# 4_AT_START_F403A_V1_2_Connectors.net
KiCad netlist of a schematic drawn in Altium Designer
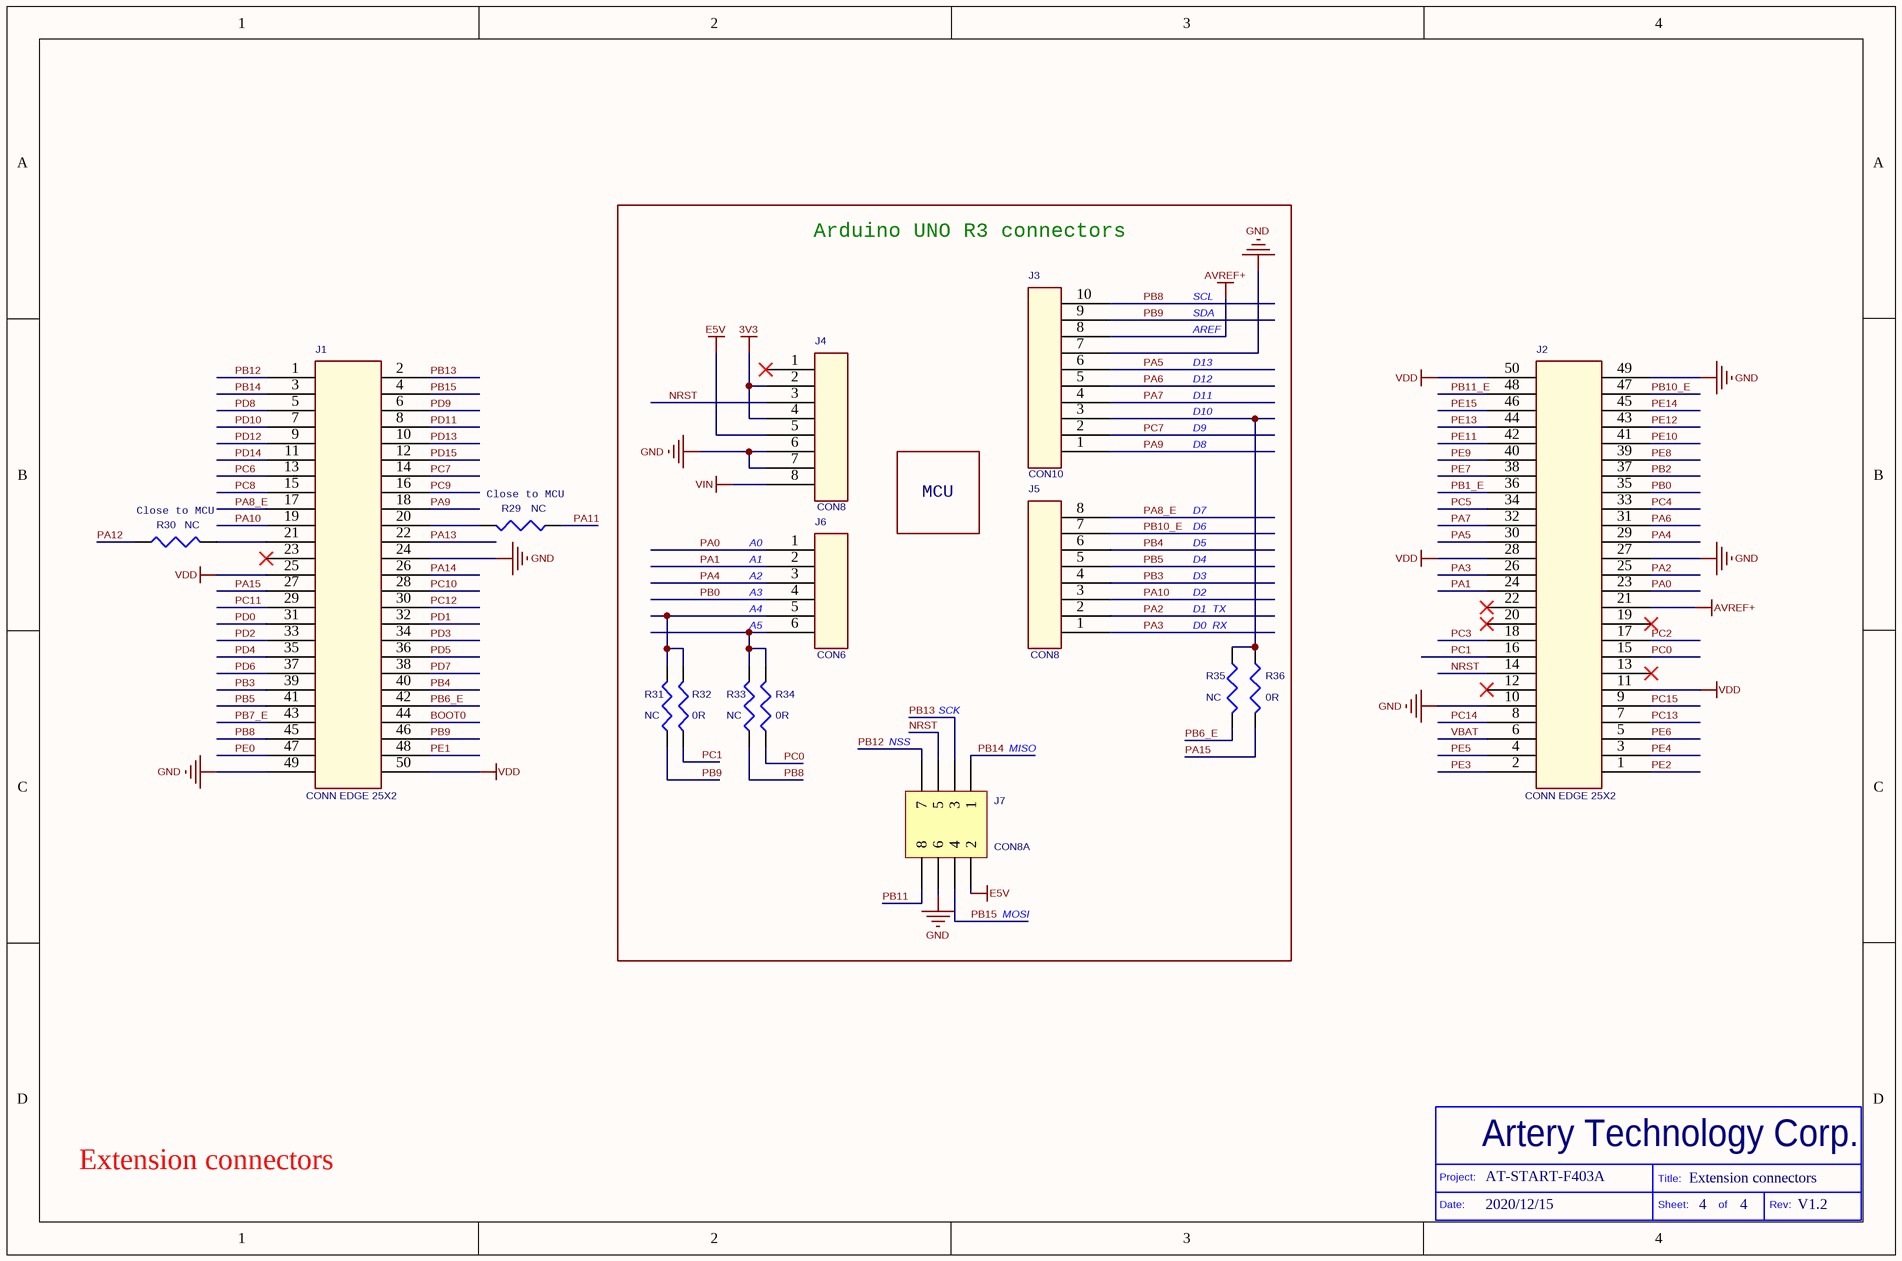
[diagram p0: 4_AT_START_F403A_V1.2_Connectors.SchDoc]

(export (version "E")
  (design (tool "Eeschema 10.0.6"))
  (components
    (comp (ref "J1")
      (value "CONN EDGE 25X2")
      (footprint "HEAD2*25")
      (libsource (lib "SCM_START_402F") (part "CONN EDGE 25X2"))
    )
    (comp (ref "J2")
      (value "CONN EDGE 25X2")
      (footprint "HEAD2*25")
      (libsource (lib "") (part "CONN EDGE 25X2_1"))
    )
    (comp (ref "J3") (value "CON10") (footprint "HDR1X10 - 2#") (libsource (lib "*") (part "CON10_0")))
    (comp (ref "J4") (value "CON8") (footprint "HDR1X8 - 2#") (libsource (lib "") (part "CON8_1")))
    (comp (ref "J5") (value "CON8") (footprint "HDR1X8 - 2#") (libsource (lib "*") (part "CON8")))
    (comp (ref "J6") (value "CON6") (footprint "HDR1X6 -2#") (libsource (lib "*") (part "CON6")))
    (comp (ref "J7")
      (value "CON8A")
      (footprint "HDR2X4")
      (description "Header, 4-Pin, Dual row")
      (fields (field (name "PUBLISHER") "Altium Limited"))
      (libsource (lib "Miscellaneous Connectors") (part "Header 4X2"))
    )
    (comp (ref "R29") (value "NC") (libsource (lib "*") (part "470,1/10W,1%,SMD0603")))
    (comp (ref "R30") (value "NC") (libsource (lib "*") (part "470,1/10W,1%,SMD0603")))
    (comp (ref "R31") (value "NC") (libsource (lib "*") (part "10K,1/10W,1%,SMD0603_Dup1")))
    (comp (ref "R32") (value "0R") (libsource (lib "*") (part "10K,1/10W,1%,SMD0603_Dup1")))
    (comp (ref "R33") (value "NC") (libsource (lib "*") (part "10K,1/10W,1%,SMD0603_Dup1")))
    (comp (ref "R34") (value "0R") (libsource (lib "*") (part "10K,1/10W,1%,SMD0603_Dup1")))
    (comp (ref "R35") (value "NC") (libsource (lib "*") (part "10K,1/10W,1%,SMD0603_Dup1")))
    (comp (ref "R36") (value "0R") (libsource (lib "*") (part "10K,1/10W,1%,SMD0603_Dup1")))
  )
  (nets
    (net (code "1") (name "/A0") (class "Default")
      (node (ref "J2") (pin "23") (pinfunction "23_23") (pintype "passive"))
      (node (ref "J6") (pin "1") (pinfunction "1_1") (pintype "passive"))
    )
    (net (code "2") (name "/A1") (class "Default")
      (node (ref "J2") (pin "24") (pinfunction "24_24") (pintype "passive"))
      (node (ref "J6") (pin "2") (pinfunction "2_2") (pintype "passive"))
    )
    (net (code "3") (name "/A2") (class "Default")
      (node (ref "J2") (pin "29") (pinfunction "29_29") (pintype "passive"))
      (node (ref "J6") (pin "3") (pinfunction "3_3") (pintype "passive"))
    )
    (net (code "4") (name "/A3") (class "Default")
      (node (ref "J2") (pin "35") (pinfunction "35_35") (pintype "passive"))
      (node (ref "J6") (pin "4") (pinfunction "4_4") (pintype "passive"))
    )
    (net (code "5") (name "/A4") (class "Default")
      (node (ref "J6") (pin "5") (pinfunction "5_5") (pintype "passive"))
      (node (ref "R31") (pin "2") (pinfunction "2_2") (pintype "passive"))
      (node (ref "R32") (pin "2") (pinfunction "2_2") (pintype "passive"))
    )
    (net (code "6") (name "/A5") (class "Default")
      (node (ref "J6") (pin "6") (pinfunction "6_6") (pintype "passive"))
      (node (ref "R33") (pin "2") (pinfunction "2_2") (pintype "passive"))
      (node (ref "R34") (pin "2") (pinfunction "2_2") (pintype "passive"))
    )
    (net (code "7") (name "/BOOT0") (class "Default")
      (node (ref "J1") (pin "44") (pinfunction "44_44") (pintype "passive"))
    )
    (net (code "8") (name "/D0") (class "Default")
      (node (ref "J2") (pin "26") (pinfunction "26_26") (pintype "passive"))
      (node (ref "J5") (pin "1") (pinfunction "1_1") (pintype "passive"))
    )
    (net (code "9") (name "/D1") (class "Default")
      (node (ref "J2") (pin "25") (pinfunction "25_25") (pintype "passive"))
      (node (ref "J5") (pin "2") (pinfunction "2_2") (pintype "passive"))
    )
    (net (code "10") (name "/D2") (class "Default")
      (node (ref "J1") (pin "19") (pinfunction "19_19") (pintype "passive"))
      (node (ref "J5") (pin "3") (pinfunction "3_3") (pintype "passive"))
    )
    (net (code "11") (name "/D3") (class "Default")
      (node (ref "J1") (pin "39") (pinfunction "39_39") (pintype "passive"))
      (node (ref "J5") (pin "4") (pinfunction "4_4") (pintype "passive"))
    )
    (net (code "12") (name "/D4") (class "Default")
      (node (ref "J1") (pin "41") (pinfunction "41_41") (pintype "passive"))
      (node (ref "J5") (pin "5") (pinfunction "5_5") (pintype "passive"))
    )
    (net (code "13") (name "/D5") (class "Default")
      (node (ref "J1") (pin "40") (pinfunction "40_40") (pintype "passive"))
      (node (ref "J5") (pin "6") (pinfunction "6_6") (pintype "passive"))
    )
    (net (code "14") (name "/D6") (class "Default")
      (node (ref "J2") (pin "47") (pinfunction "47_47") (pintype "passive"))
      (node (ref "J5") (pin "7") (pinfunction "7_7") (pintype "passive"))
    )
    (net (code "15") (name "/D7") (class "Default")
      (node (ref "J1") (pin "17") (pinfunction "17_17") (pintype "passive"))
      (node (ref "J5") (pin "8") (pinfunction "8_8") (pintype "passive"))
    )
    (net (code "16") (name "/D8") (class "Default")
      (node (ref "J1") (pin "18") (pinfunction "18_18") (pintype "passive"))
      (node (ref "J3") (pin "1") (pinfunction "1_1") (pintype "passive"))
    )
    (net (code "17") (name "/D9") (class "Default")
      (node (ref "J1") (pin "14") (pinfunction "14_14") (pintype "passive"))
      (node (ref "J3") (pin "2") (pinfunction "2_2") (pintype "passive"))
    )
    (net (code "18") (name "/D10") (class "Default")
      (node (ref "J3") (pin "3") (pinfunction "3_3") (pintype "passive"))
      (node (ref "R35") (pin "1") (pinfunction "1_1") (pintype "passive"))
      (node (ref "R36") (pin "1") (pinfunction "1_1") (pintype "passive"))
    )
    (net (code "19") (name "/D11") (class "Default")
      (node (ref "J2") (pin "32") (pinfunction "32_32") (pintype "passive"))
      (node (ref "J3") (pin "4") (pinfunction "4_4") (pintype "passive"))
    )
    (net (code "20") (name "/D12") (class "Default")
      (node (ref "J2") (pin "31") (pinfunction "31_31") (pintype "passive"))
      (node (ref "J3") (pin "5") (pinfunction "5_5") (pintype "passive"))
    )
    (net (code "21") (name "/D13") (class "Default")
      (node (ref "J2") (pin "30") (pinfunction "30_30") (pintype "passive"))
      (node (ref "J3") (pin "6") (pinfunction "6_6") (pintype "passive"))
    )
    (net (code "22") (name "/NRST") (class "Default")
      (node (ref "J2") (pin "14") (pinfunction "14_14") (pintype "passive"))
      (node (ref "J4") (pin "3") (pinfunction "3_3") (pintype "passive"))
      (node (ref "J7") (pin "5") (pinfunction "5_5") (pintype "passive"))
    )
    (net (code "23") (name "/PA11") (class "Default")
      (node (ref "R29") (pin "1") (pinfunction "1_1") (pintype "passive"))
    )
    (net (code "24") (name "/PA12") (class "Default")
      (node (ref "R30") (pin "1") (pinfunction "1_1") (pintype "passive"))
    )
    (net (code "25") (name "/PA13") (class "Default")
      (node (ref "J1") (pin "22") (pinfunction "22_22") (pintype "passive"))
    )
    (net (code "26") (name "/PA14") (class "Default")
      (node (ref "J1") (pin "26") (pinfunction "26_26") (pintype "passive"))
    )
    (net (code "27") (name "/PA15") (class "Default")
      (node (ref "J1") (pin "27") (pinfunction "27_27") (pintype "passive"))
      (node (ref "R36") (pin "2") (pinfunction "2_2") (pintype "passive"))
    )
    (net (code "28") (name "/PB1_E") (class "Default")
      (node (ref "J2") (pin "36") (pinfunction "36_36") (pintype "passive"))
    )
    (net (code "29") (name "/PB2") (class "Default")
      (node (ref "J2") (pin "37") (pinfunction "37_37") (pintype "passive"))
    )
    (net (code "30") (name "/PB6_E") (class "Default")
      (node (ref "J1") (pin "42") (pinfunction "42_42") (pintype "passive"))
      (node (ref "R35") (pin "2") (pinfunction "2_2") (pintype "passive"))
    )
    (net (code "31") (name "/PB7_E") (class "Default")
      (node (ref "J1") (pin "43") (pinfunction "43_43") (pintype "passive"))
    )
    (net (code "32") (name "/PB8") (class "Default")
      (node (ref "J1") (pin "45") (pinfunction "45_45") (pintype "passive"))
      (node (ref "J3") (pin "10") (pinfunction "10_10") (pintype "passive"))
      (node (ref "R33") (pin "1") (pinfunction "1_1") (pintype "passive"))
    )
    (net (code "33") (name "/PB9") (class "Default")
      (node (ref "J1") (pin "46") (pinfunction "46_46") (pintype "passive"))
      (node (ref "J3") (pin "9") (pinfunction "9_9") (pintype "passive"))
      (node (ref "R31") (pin "1") (pinfunction "1_1") (pintype "passive"))
    )
    (net (code "34") (name "/PB11") (class "Default")
      (node (ref "J7") (pin "8") (pinfunction "8_8") (pintype "passive"))
    )
    (net (code "35") (name "/PB11_E") (class "Default")
      (node (ref "J2") (pin "48") (pinfunction "48_48") (pintype "passive"))
    )
    (net (code "36") (name "/PB12") (class "Default")
      (node (ref "J1") (pin "1") (pinfunction "1_1") (pintype "passive"))
      (node (ref "J7") (pin "7") (pinfunction "7_7") (pintype "passive"))
    )
    (net (code "37") (name "/PB13") (class "Default")
      (node (ref "J1") (pin "2") (pinfunction "2_2") (pintype "passive"))
      (node (ref "J7") (pin "3") (pinfunction "3_3") (pintype "passive"))
    )
    (net (code "38") (name "/PB14") (class "Default")
      (node (ref "J1") (pin "3") (pinfunction "3_3") (pintype "passive"))
      (node (ref "J7") (pin "1") (pinfunction "1_1") (pintype "passive"))
    )
    (net (code "39") (name "/PB15") (class "Default")
      (node (ref "J1") (pin "4") (pinfunction "4_4") (pintype "passive"))
      (node (ref "J7") (pin "4") (pinfunction "4_4") (pintype "passive"))
    )
    (net (code "40") (name "/PC0") (class "Default")
      (node (ref "J2") (pin "15") (pinfunction "15_15") (pintype "passive"))
      (node (ref "R34") (pin "1") (pinfunction "1_1") (pintype "passive"))
    )
    (net (code "41") (name "/PC1") (class "Default")
      (node (ref "J2") (pin "16") (pinfunction "16_16") (pintype "passive"))
      (node (ref "R32") (pin "1") (pinfunction "1_1") (pintype "passive"))
    )
    (net (code "42") (name "/PC2") (class "Default")
      (node (ref "J2") (pin "17") (pinfunction "17_17") (pintype "passive"))
    )
    (net (code "43") (name "/PC3") (class "Default")
      (node (ref "J2") (pin "18") (pinfunction "18_18") (pintype "passive"))
    )
    (net (code "44") (name "/PC4") (class "Default")
      (node (ref "J2") (pin "33") (pinfunction "33_33") (pintype "passive"))
    )
    (net (code "45") (name "/PC5") (class "Default")
      (node (ref "J2") (pin "34") (pinfunction "34_34") (pintype "passive"))
    )
    (net (code "46") (name "/PC6") (class "Default")
      (node (ref "J1") (pin "13") (pinfunction "13_13") (pintype "passive"))
    )
    (net (code "47") (name "/PC8") (class "Default")
      (node (ref "J1") (pin "15") (pinfunction "15_15") (pintype "passive"))
    )
    (net (code "48") (name "/PC9") (class "Default")
      (node (ref "J1") (pin "16") (pinfunction "16_16") (pintype "passive"))
    )
    (net (code "49") (name "/PC10") (class "Default")
      (node (ref "J1") (pin "28") (pinfunction "28_28") (pintype "passive"))
    )
    (net (code "50") (name "/PC11") (class "Default")
      (node (ref "J1") (pin "29") (pinfunction "29_29") (pintype "passive"))
    )
    (net (code "51") (name "/PC12") (class "Default")
      (node (ref "J1") (pin "30") (pinfunction "30_30") (pintype "passive"))
    )
    (net (code "52") (name "/PC13") (class "Default")
      (node (ref "J2") (pin "7") (pinfunction "7_7") (pintype "passive"))
    )
    (net (code "53") (name "/PC14") (class "Default")
      (node (ref "J2") (pin "8") (pinfunction "8_8") (pintype "passive"))
    )
    (net (code "54") (name "/PC15") (class "Default")
      (node (ref "J2") (pin "9") (pinfunction "9_9") (pintype "passive"))
    )
    (net (code "55") (name "/PD0") (class "Default")
      (node (ref "J1") (pin "31") (pinfunction "31_31") (pintype "passive"))
    )
    (net (code "56") (name "/PD1") (class "Default")
      (node (ref "J1") (pin "32") (pinfunction "32_32") (pintype "passive"))
    )
    (net (code "57") (name "/PD2") (class "Default")
      (node (ref "J1") (pin "33") (pinfunction "33_33") (pintype "passive"))
    )
    (net (code "58") (name "/PD3") (class "Default")
      (node (ref "J1") (pin "34") (pinfunction "34_34") (pintype "passive"))
    )
    (net (code "59") (name "/PD4") (class "Default")
      (node (ref "J1") (pin "35") (pinfunction "35_35") (pintype "passive"))
    )
    (net (code "60") (name "/PD5") (class "Default")
      (node (ref "J1") (pin "36") (pinfunction "36_36") (pintype "passive"))
    )
    (net (code "61") (name "/PD6") (class "Default")
      (node (ref "J1") (pin "37") (pinfunction "37_37") (pintype "passive"))
    )
    (net (code "62") (name "/PD7") (class "Default")
      (node (ref "J1") (pin "38") (pinfunction "38_38") (pintype "passive"))
    )
    (net (code "63") (name "/PD8") (class "Default")
      (node (ref "J1") (pin "5") (pinfunction "5_5") (pintype "passive"))
    )
    (net (code "64") (name "/PD9") (class "Default")
      (node (ref "J1") (pin "6") (pinfunction "6_6") (pintype "passive"))
    )
    (net (code "65") (name "/PD10") (class "Default")
      (node (ref "J1") (pin "7") (pinfunction "7_7") (pintype "passive"))
    )
    (net (code "66") (name "/PD11") (class "Default")
      (node (ref "J1") (pin "8") (pinfunction "8_8") (pintype "passive"))
    )
    (net (code "67") (name "/PD12") (class "Default")
      (node (ref "J1") (pin "9") (pinfunction "9_9") (pintype "passive"))
    )
    (net (code "68") (name "/PD13") (class "Default")
      (node (ref "J1") (pin "10") (pinfunction "10_10") (pintype "passive"))
    )
    (net (code "69") (name "/PD14") (class "Default")
      (node (ref "J1") (pin "11") (pinfunction "11_11") (pintype "passive"))
    )
    (net (code "70") (name "/PD15") (class "Default")
      (node (ref "J1") (pin "12") (pinfunction "12_12") (pintype "passive"))
    )
    (net (code "71") (name "/PE0") (class "Default")
      (node (ref "J1") (pin "47") (pinfunction "47_47") (pintype "passive"))
    )
    (net (code "72") (name "/PE1") (class "Default")
      (node (ref "J1") (pin "48") (pinfunction "48_48") (pintype "passive"))
    )
    (net (code "73") (name "/PE2") (class "Default")
      (node (ref "J2") (pin "1") (pinfunction "1_1") (pintype "passive"))
    )
    (net (code "74") (name "/PE3") (class "Default")
      (node (ref "J2") (pin "2") (pinfunction "2_2") (pintype "passive"))
    )
    (net (code "75") (name "/PE4") (class "Default")
      (node (ref "J2") (pin "3") (pinfunction "3_3") (pintype "passive"))
    )
    (net (code "76") (name "/PE5") (class "Default")
      (node (ref "J2") (pin "4") (pinfunction "4_4") (pintype "passive"))
    )
    (net (code "77") (name "/PE6") (class "Default")
      (node (ref "J2") (pin "5") (pinfunction "5_5") (pintype "passive"))
    )
    (net (code "78") (name "/PE7") (class "Default")
      (node (ref "J2") (pin "38") (pinfunction "38_38") (pintype "passive"))
    )
    (net (code "79") (name "/PE8") (class "Default")
      (node (ref "J2") (pin "39") (pinfunction "39_39") (pintype "passive"))
    )
    (net (code "80") (name "/PE9") (class "Default")
      (node (ref "J2") (pin "40") (pinfunction "40_40") (pintype "passive"))
    )
    (net (code "81") (name "/PE10") (class "Default")
      (node (ref "J2") (pin "41") (pinfunction "41_41") (pintype "passive"))
    )
    (net (code "82") (name "/PE11") (class "Default")
      (node (ref "J2") (pin "42") (pinfunction "42_42") (pintype "passive"))
    )
    (net (code "83") (name "/PE12") (class "Default")
      (node (ref "J2") (pin "43") (pinfunction "43_43") (pintype "passive"))
    )
    (net (code "84") (name "/PE13") (class "Default")
      (node (ref "J2") (pin "44") (pinfunction "44_44") (pintype "passive"))
    )
    (net (code "85") (name "/PE14") (class "Default")
      (node (ref "J2") (pin "45") (pinfunction "45_45") (pintype "passive"))
    )
    (net (code "86") (name "/PE15") (class "Default")
      (node (ref "J2") (pin "46") (pinfunction "46_46") (pintype "passive"))
    )
    (net (code "87") (name "/VBAT") (class "Default")
      (node (ref "J2") (pin "6") (pinfunction "6_6") (pintype "passive"))
    )
    (net (code "88") (name "3V3") (class "Default")
      (node (ref "J4") (pin "2") (pinfunction "2_2") (pintype "passive"))
      (node (ref "J4") (pin "4") (pinfunction "4_4") (pintype "passive"))
    )
    (net (code "89") (name "AVREF+") (class "Default")
      (node (ref "J2") (pin "21") (pinfunction "21_21") (pintype "passive"))
      (node (ref "J3") (pin "8") (pinfunction "8_8") (pintype "passive"))
    )
    (net (code "90") (name "E5V") (class "Default")
      (node (ref "J4") (pin "5") (pinfunction "5_5") (pintype "passive"))
      (node (ref "J7") (pin "2") (pinfunction "2_2") (pintype "passive"))
    )
    (net (code "91") (name "GND") (class "Default")
      (node (ref "J1") (pin "24") (pinfunction "24_24") (pintype "passive"))
      (node (ref "J1") (pin "49") (pinfunction "49_49") (pintype "passive"))
      (node (ref "J2") (pin "10") (pinfunction "10_10") (pintype "passive"))
      (node (ref "J2") (pin "27") (pinfunction "27_27") (pintype "passive"))
      (node (ref "J2") (pin "49") (pinfunction "49_49") (pintype "passive"))
      (node (ref "J3") (pin "7") (pinfunction "7_7") (pintype "passive"))
      (node (ref "J4") (pin "6") (pinfunction "6_6") (pintype "passive"))
      (node (ref "J4") (pin "7") (pinfunction "7_7") (pintype "passive"))
      (node (ref "J7") (pin "6") (pinfunction "6_6") (pintype "passive"))
    )
    (net (code "92") (name "Net-(J1-Pad20)") (class "Default")
      (node (ref "J1") (pin "20") (pinfunction "20_20") (pintype "passive"))
      (node (ref "R29") (pin "2") (pinfunction "2_2") (pintype "passive"))
    )
    (net (code "93") (name "Net-(J1-Pad21)") (class "Default")
      (node (ref "J1") (pin "21") (pinfunction "21_21") (pintype "passive"))
      (node (ref "R30") (pin "2") (pinfunction "2_2") (pintype "passive"))
    )
    (net (code "94") (name "VDD") (class "Default")
      (node (ref "J1") (pin "25") (pinfunction "25_25") (pintype "passive"))
      (node (ref "J1") (pin "50") (pinfunction "50_50") (pintype "passive"))
      (node (ref "J2") (pin "11") (pinfunction "11_11") (pintype "passive"))
      (node (ref "J2") (pin "28") (pinfunction "28_28") (pintype "passive"))
      (node (ref "J2") (pin "50") (pinfunction "50_50") (pintype "passive"))
    )
    (net (code "95") (name "VIN") (class "Default")
      (node (ref "J4") (pin "8") (pinfunction "8_8") (pintype "passive"))
    )
    (net (code "96") (name "unconnected-(J1-Pad23)") (class "Default")
      (node (ref "J1") (pin "23") (pinfunction "23_23") (pintype "passive+no_connect"))
    )
    (net (code "97") (name "unconnected-(J2-Pad12)") (class "Default")
      (node (ref "J2") (pin "12") (pinfunction "12_12") (pintype "passive+no_connect"))
    )
    (net (code "98") (name "unconnected-(J2-Pad13)") (class "Default")
      (node (ref "J2") (pin "13") (pinfunction "13_13") (pintype "passive+no_connect"))
    )
    (net (code "99") (name "unconnected-(J2-Pad19)") (class "Default")
      (node (ref "J2") (pin "19") (pinfunction "19_19") (pintype "passive+no_connect"))
    )
    (net (code "100") (name "unconnected-(J2-Pad20)") (class "Default")
      (node (ref "J2") (pin "20") (pinfunction "20_20") (pintype "passive+no_connect"))
    )
    (net (code "101") (name "unconnected-(J2-Pad22)") (class "Default")
      (node (ref "J2") (pin "22") (pinfunction "22_22") (pintype "passive+no_connect"))
    )
    (net (code "102") (name "unconnected-(J4-Pad1)") (class "Default")
      (node (ref "J4") (pin "1") (pinfunction "1_1") (pintype "passive+no_connect"))
    )
  )
)
